# followLineSensor.net
KiCad netlist of a schematic drawn in EAGLE
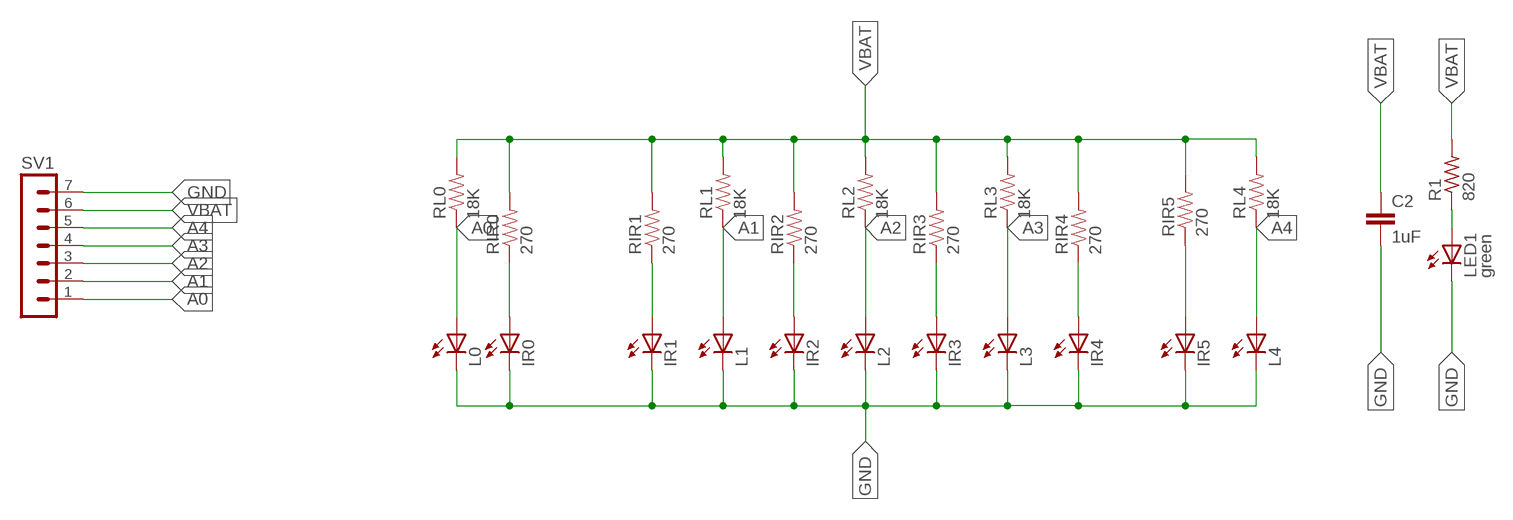
[diagram p0: schematic, sheet 1]

(export (version "E")
  (design (tool "Eeschema 10.0.6"))
  (components
    (comp (ref "C2")
      (value "1uF")
      (footprint "eagle-import:C1206")
      (libsource (lib "eagle-import") (part "C-EUC1206"))
    )
    (comp (ref "IR0")
      (value "LED5MM")
      (footprint "eagle-import:LED5MM")
      (libsource (lib "eagle-import") (part "LED5MM"))
    )
    (comp (ref "IR1")
      (value "LED5MM")
      (footprint "eagle-import:LED5MM")
      (libsource (lib "eagle-import") (part "LED5MM"))
    )
    (comp (ref "IR2")
      (value "LED5MM")
      (footprint "eagle-import:LED5MM")
      (libsource (lib "eagle-import") (part "LED5MM"))
    )
    (comp (ref "IR3")
      (value "LED5MM")
      (footprint "eagle-import:LED5MM")
      (libsource (lib "eagle-import") (part "LED5MM"))
    )
    (comp (ref "IR4")
      (value "LED5MM")
      (footprint "eagle-import:LED5MM")
      (libsource (lib "eagle-import") (part "LED5MM"))
    )
    (comp (ref "IR5")
      (value "LED5MM")
      (footprint "eagle-import:LED5MM")
      (libsource (lib "eagle-import") (part "LED5MM"))
    )
    (comp (ref "L0")
      (value "LED5MM")
      (footprint "eagle-import:LED5MM")
      (libsource (lib "eagle-import") (part "LED5MM"))
    )
    (comp (ref "L1")
      (value "LED5MM")
      (footprint "eagle-import:LED5MM")
      (libsource (lib "eagle-import") (part "LED5MM"))
    )
    (comp (ref "L2")
      (value "LED5MM")
      (footprint "eagle-import:LED5MM")
      (libsource (lib "eagle-import") (part "LED5MM"))
    )
    (comp (ref "L3")
      (value "LED5MM")
      (footprint "eagle-import:LED5MM")
      (libsource (lib "eagle-import") (part "LED5MM"))
    )
    (comp (ref "L4")
      (value "LED5MM")
      (footprint "eagle-import:LED5MM")
      (libsource (lib "eagle-import") (part "LED5MM"))
    )
    (comp (ref "LED1")
      (value "green")
      (footprint "eagle-import:SML0805")
      (libsource (lib "eagle-import") (part "LEDSML0805"))
    )
    (comp (ref "R1")
      (value "820")
      (footprint "eagle-import:R0805")
      (libsource (lib "eagle-import") (part "R-US_R0805"))
    )
    (comp (ref "RIR0")
      (value "270")
      (footprint "eagle-import:1206")
      (libsource (lib "eagle-import") (part "RESISTOR1206"))
    )
    (comp (ref "RIR1")
      (value "270")
      (footprint "eagle-import:1206")
      (libsource (lib "eagle-import") (part "RESISTOR1206"))
    )
    (comp (ref "RIR2")
      (value "270")
      (footprint "eagle-import:1206")
      (libsource (lib "eagle-import") (part "RESISTOR1206"))
    )
    (comp (ref "RIR3")
      (value "270")
      (footprint "eagle-import:1206")
      (libsource (lib "eagle-import") (part "RESISTOR1206"))
    )
    (comp (ref "RIR4")
      (value "270")
      (footprint "eagle-import:1206")
      (libsource (lib "eagle-import") (part "RESISTOR1206"))
    )
    (comp (ref "RIR5")
      (value "270")
      (footprint "eagle-import:1206")
      (libsource (lib "eagle-import") (part "RESISTOR1206"))
    )
    (comp (ref "RL0")
      (value "18K")
      (footprint "eagle-import:1206")
      (libsource (lib "eagle-import") (part "RESISTOR1206"))
    )
    (comp (ref "RL1")
      (value "18K")
      (footprint "eagle-import:1206")
      (libsource (lib "eagle-import") (part "RESISTOR1206"))
    )
    (comp (ref "RL2")
      (value "18K")
      (footprint "eagle-import:1206")
      (libsource (lib "eagle-import") (part "RESISTOR1206"))
    )
    (comp (ref "RL3")
      (value "18K")
      (footprint "eagle-import:1206")
      (libsource (lib "eagle-import") (part "RESISTOR1206"))
    )
    (comp (ref "RL4")
      (value "18K")
      (footprint "eagle-import:1206")
      (libsource (lib "eagle-import") (part "RESISTOR1206"))
    )
    (comp (ref "SV1")
      (value "MA07-1")
      (footprint "eagle-import:MA07-1")
      (libsource (lib "eagle-import") (part "MA07-1"))
    )
  )
  (nets
    (net (code "1") (name "A0") (class "Default")
      (node (ref "L0") (pin "A") (pinfunction "A_A") (pintype "passive"))
      (node (ref "RL0") (pin "1") (pinfunction "1_1") (pintype "passive"))
      (node (ref "SV1") (pin "1") (pinfunction "1_1") (pintype "passive"))
    )
    (net (code "2") (name "A1") (class "Default")
      (node (ref "L1") (pin "A") (pinfunction "A_A") (pintype "passive"))
      (node (ref "RL1") (pin "1") (pinfunction "1_1") (pintype "passive"))
      (node (ref "SV1") (pin "2") (pinfunction "2_2") (pintype "passive"))
    )
    (net (code "3") (name "A2") (class "Default")
      (node (ref "L2") (pin "A") (pinfunction "A_A") (pintype "passive"))
      (node (ref "RL2") (pin "1") (pinfunction "1_1") (pintype "passive"))
      (node (ref "SV1") (pin "3") (pinfunction "3_3") (pintype "passive"))
    )
    (net (code "4") (name "A3") (class "Default")
      (node (ref "L3") (pin "A") (pinfunction "A_A") (pintype "passive"))
      (node (ref "RL3") (pin "1") (pinfunction "1_1") (pintype "passive"))
      (node (ref "SV1") (pin "4") (pinfunction "4_4") (pintype "passive"))
    )
    (net (code "5") (name "A4") (class "Default")
      (node (ref "L4") (pin "A") (pinfunction "A_A") (pintype "passive"))
      (node (ref "RL4") (pin "1") (pinfunction "1_1") (pintype "passive"))
      (node (ref "SV1") (pin "5") (pinfunction "5_5") (pintype "passive"))
    )
    (net (code "6") (name "GND") (class "Default")
      (node (ref "C2") (pin "2") (pinfunction "2_2") (pintype "passive"))
      (node (ref "IR0") (pin "K") (pinfunction "C_K") (pintype "passive"))
      (node (ref "IR1") (pin "K") (pinfunction "C_K") (pintype "passive"))
      (node (ref "IR2") (pin "K") (pinfunction "C_K") (pintype "passive"))
      (node (ref "IR3") (pin "K") (pinfunction "C_K") (pintype "passive"))
      (node (ref "IR4") (pin "K") (pinfunction "C_K") (pintype "passive"))
      (node (ref "IR5") (pin "K") (pinfunction "C_K") (pintype "passive"))
      (node (ref "L0") (pin "K") (pinfunction "C_K") (pintype "passive"))
      (node (ref "L1") (pin "K") (pinfunction "C_K") (pintype "passive"))
      (node (ref "L2") (pin "K") (pinfunction "C_K") (pintype "passive"))
      (node (ref "L3") (pin "K") (pinfunction "C_K") (pintype "passive"))
      (node (ref "L4") (pin "K") (pinfunction "C_K") (pintype "passive"))
      (node (ref "LED1") (pin "C") (pinfunction "C_C") (pintype "passive"))
      (node (ref "SV1") (pin "7") (pinfunction "7_7") (pintype "passive"))
    )
    (net (code "7") (name "Net-(IR0-PadA)") (class "Default")
      (node (ref "IR0") (pin "A") (pinfunction "A_A") (pintype "passive"))
      (node (ref "RIR0") (pin "1") (pinfunction "1_1") (pintype "passive"))
    )
    (net (code "8") (name "Net-(IR1-PadA)") (class "Default")
      (node (ref "IR1") (pin "A") (pinfunction "A_A") (pintype "passive"))
      (node (ref "RIR1") (pin "1") (pinfunction "1_1") (pintype "passive"))
    )
    (net (code "9") (name "Net-(IR2-PadA)") (class "Default")
      (node (ref "IR2") (pin "A") (pinfunction "A_A") (pintype "passive"))
      (node (ref "RIR2") (pin "1") (pinfunction "1_1") (pintype "passive"))
    )
    (net (code "10") (name "Net-(IR3-PadA)") (class "Default")
      (node (ref "IR3") (pin "A") (pinfunction "A_A") (pintype "passive"))
      (node (ref "RIR3") (pin "1") (pinfunction "1_1") (pintype "passive"))
    )
    (net (code "11") (name "Net-(IR4-PadA)") (class "Default")
      (node (ref "IR4") (pin "A") (pinfunction "A_A") (pintype "passive"))
      (node (ref "RIR4") (pin "1") (pinfunction "1_1") (pintype "passive"))
    )
    (net (code "12") (name "Net-(IR5-PadA)") (class "Default")
      (node (ref "IR5") (pin "A") (pinfunction "A_A") (pintype "passive"))
      (node (ref "RIR5") (pin "1") (pinfunction "1_1") (pintype "passive"))
    )
    (net (code "13") (name "Net-(LED1-PadA)") (class "Default")
      (node (ref "LED1") (pin "A") (pinfunction "A_A") (pintype "passive"))
      (node (ref "R1") (pin "1") (pinfunction "1_1") (pintype "passive"))
    )
    (net (code "14") (name "VBAT") (class "Default")
      (node (ref "C2") (pin "1") (pinfunction "1_1") (pintype "passive"))
      (node (ref "R1") (pin "2") (pinfunction "2_2") (pintype "passive"))
      (node (ref "RIR0") (pin "2") (pinfunction "2_2") (pintype "passive"))
      (node (ref "RIR1") (pin "2") (pinfunction "2_2") (pintype "passive"))
      (node (ref "RIR2") (pin "2") (pinfunction "2_2") (pintype "passive"))
      (node (ref "RIR3") (pin "2") (pinfunction "2_2") (pintype "passive"))
      (node (ref "RIR4") (pin "2") (pinfunction "2_2") (pintype "passive"))
      (node (ref "RIR5") (pin "2") (pinfunction "2_2") (pintype "passive"))
      (node (ref "RL0") (pin "2") (pinfunction "2_2") (pintype "passive"))
      (node (ref "RL1") (pin "2") (pinfunction "2_2") (pintype "passive"))
      (node (ref "RL2") (pin "2") (pinfunction "2_2") (pintype "passive"))
      (node (ref "RL3") (pin "2") (pinfunction "2_2") (pintype "passive"))
      (node (ref "RL4") (pin "2") (pinfunction "2_2") (pintype "passive"))
      (node (ref "SV1") (pin "6") (pinfunction "6_6") (pintype "passive"))
    )
  )
)
